# CarBot_Pedro.net
KiCad netlist of a schematic drawn in EAGLE
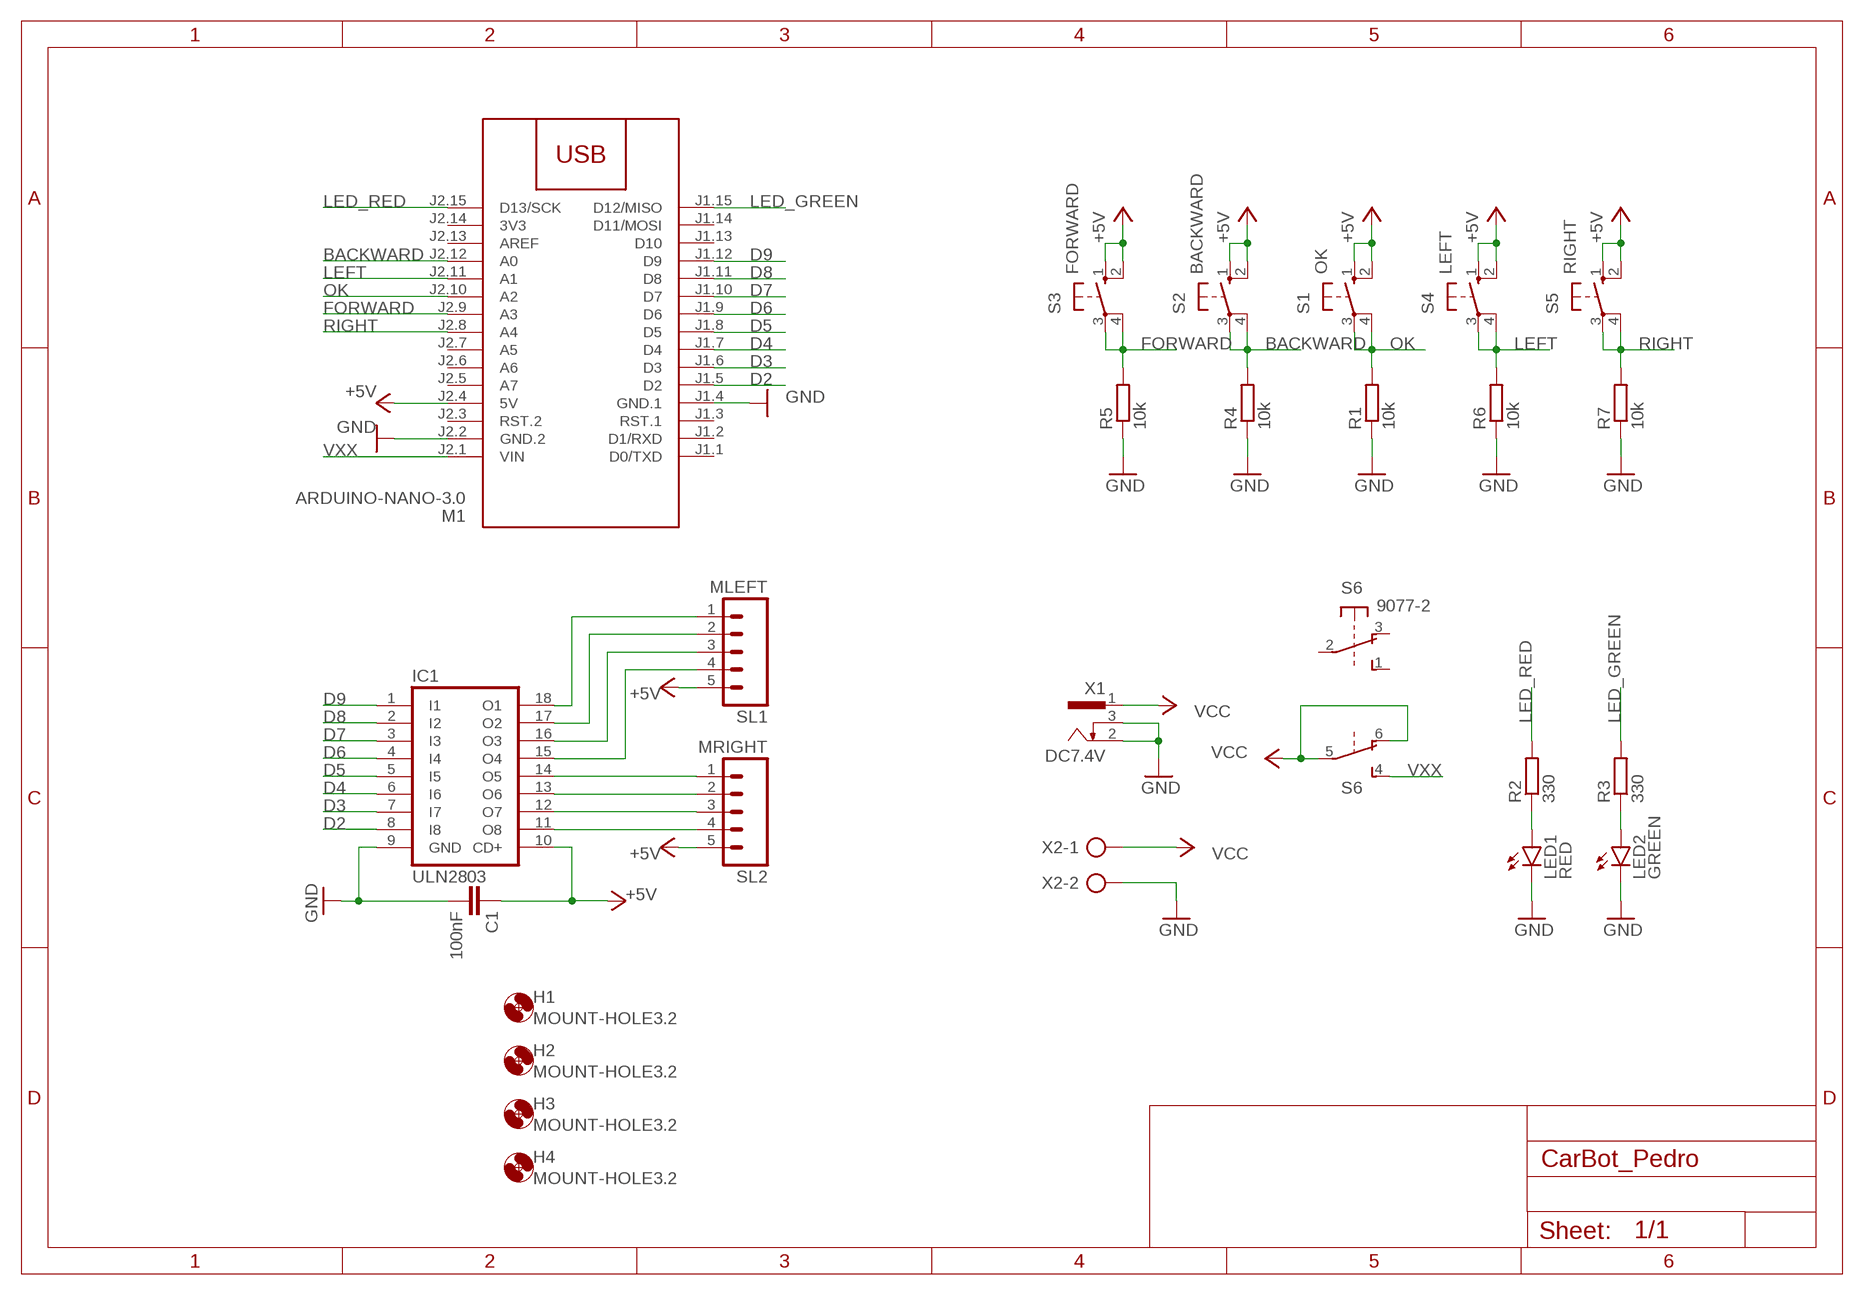
[diagram p0: schematic, sheet 1]

(export (version "E")
  (design (tool "Eeschema 10.0.6"))
  (components
    (comp (ref "C1")
      (value "100nF")
      (footprint "eagle-import:C025-030X050")
      (libsource (lib "eagle-import") (part "C-EU025-030X050"))
    )
    (comp (ref "H1")
      (value "MOUNT-HOLE3.2")
      (footprint "eagle-import:3,2")
      (libsource (lib "eagle-import") (part "MOUNT-HOLE3.2"))
    )
    (comp (ref "H2")
      (value "MOUNT-HOLE3.2")
      (footprint "eagle-import:3,2")
      (libsource (lib "eagle-import") (part "MOUNT-HOLE3.2"))
    )
    (comp (ref "H3")
      (value "MOUNT-HOLE3.2")
      (footprint "eagle-import:3,2")
      (libsource (lib "eagle-import") (part "MOUNT-HOLE3.2"))
    )
    (comp (ref "H4")
      (value "MOUNT-HOLE3.2")
      (footprint "eagle-import:3,2")
      (libsource (lib "eagle-import") (part "MOUNT-HOLE3.2"))
    )
    (comp (ref "IC1")
      (value "ULN2803")
      (footprint "eagle-import:DIL18")
      (libsource (lib "eagle-import") (part "ULN2803A"))
    )
    (comp (ref "LED1")
      (value "RED")
      (footprint "eagle-import:LED3MM")
      (libsource (lib "eagle-import") (part "LED3MM"))
    )
    (comp (ref "LED2")
      (value "GREEN")
      (footprint "eagle-import:LED3MM")
      (libsource (lib "eagle-import") (part "LED3MM"))
    )
    (comp (ref "M1")
      (value "ARDUINO-NANO-3.0")
      (footprint "eagle-import:ARDUINO-NANO-3.0")
      (libsource (lib "eagle-import") (part "ARDUINO-NANO-3.0"))
    )
    (comp (ref "R1")
      (value "10k")
      (footprint "eagle-import:0207_7")
      (libsource (lib "eagle-import") (part "R-EU_0207/7"))
    )
    (comp (ref "R2")
      (value "330")
      (footprint "eagle-import:0207_7")
      (libsource (lib "eagle-import") (part "R-EU_0207/7"))
    )
    (comp (ref "R3")
      (value "330")
      (footprint "eagle-import:0207_7")
      (libsource (lib "eagle-import") (part "R-EU_0207/7"))
    )
    (comp (ref "R4")
      (value "10k")
      (footprint "eagle-import:0207_7")
      (libsource (lib "eagle-import") (part "R-EU_0207/7"))
    )
    (comp (ref "R5")
      (value "10k")
      (footprint "eagle-import:0207_7")
      (libsource (lib "eagle-import") (part "R-EU_0207/7"))
    )
    (comp (ref "R6")
      (value "10k")
      (footprint "eagle-import:0207_7")
      (libsource (lib "eagle-import") (part "R-EU_0207/7"))
    )
    (comp (ref "R7")
      (value "10k")
      (footprint "eagle-import:0207_7")
      (libsource (lib "eagle-import") (part "R-EU_0207/7"))
    )
    (comp (ref "S1")
      (value "OK")
      (footprint "eagle-import:B3F-40XX")
      (fields (field (name "MF") "OMRON COMPONENTS USA") (field (name "MPN") "B3F-4000"))
      (libsource (lib "eagle-import") (part "40-XX"))
    )
    (comp (ref "S2")
      (value "BACKWARD")
      (footprint "eagle-import:B3F-40XX")
      (fields (field (name "MF") "OMRON COMPONENTS USA") (field (name "MPN") "B3F-4000"))
      (libsource (lib "eagle-import") (part "40-XX"))
    )
    (comp (ref "S3")
      (value "FORWARD")
      (footprint "eagle-import:B3F-40XX")
      (fields (field (name "MF") "OMRON COMPONENTS USA") (field (name "MPN") "B3F-4000"))
      (libsource (lib "eagle-import") (part "40-XX"))
    )
    (comp (ref "S4")
      (value "LEFT")
      (footprint "eagle-import:B3F-40XX")
      (fields (field (name "MF") "OMRON COMPONENTS USA") (field (name "MPN") "B3F-4000"))
      (libsource (lib "eagle-import") (part "40-XX"))
    )
    (comp (ref "S5")
      (value "RIGHT")
      (footprint "eagle-import:B3F-40XX")
      (fields (field (name "MF") "OMRON COMPONENTS USA") (field (name "MPN") "B3F-4000"))
      (libsource (lib "eagle-import") (part "40-XX"))
    )
    (comp (ref "S6")
      (value "9077-2")
      (footprint "eagle-import:9077-2")
      (libsource (lib "eagle-import") (part "9077-2"))
    )
    (comp (ref "SL1")
      (value "MLEFT")
      (footprint "eagle-import:05P")
      (libsource (lib "eagle-import") (part "M05"))
    )
    (comp (ref "SL2")
      (value "MRIGHT")
      (footprint "eagle-import:05P")
      (libsource (lib "eagle-import") (part "M05"))
    )
    (comp (ref "X1")
      (value "DC7.4V")
      (footprint "eagle-import:733980-62")
      (libsource (lib "eagle-import") (part "73398?0-62"))
    )
    (comp (ref "X2")
      (value "AK500/2-H")
      (footprint "eagle-import:AK500_2-H")
      (libsource (lib "eagle-import") (part "AK500/2-H"))
    )
  )
  (nets
    (net (code "1") (name "+5V") (class "Default")
      (node (ref "C1") (pin "1") (pinfunction "1_1") (pintype "passive"))
      (node (ref "IC1") (pin "10") (pinfunction "CD+_10") (pintype "passive"))
      (node (ref "M1") (pin "J2.4") (pinfunction "5V_J2.4") (pintype "power_in"))
      (node (ref "S1") (pin "1") (pinfunction "S_1") (pintype "passive"))
      (node (ref "S1") (pin "2") (pinfunction "S1_2") (pintype "passive"))
      (node (ref "S2") (pin "1") (pinfunction "S_1") (pintype "passive"))
      (node (ref "S2") (pin "2") (pinfunction "S1_2") (pintype "passive"))
      (node (ref "S3") (pin "1") (pinfunction "S_1") (pintype "passive"))
      (node (ref "S3") (pin "2") (pinfunction "S1_2") (pintype "passive"))
      (node (ref "S4") (pin "1") (pinfunction "S_1") (pintype "passive"))
      (node (ref "S4") (pin "2") (pinfunction "S1_2") (pintype "passive"))
      (node (ref "S5") (pin "1") (pinfunction "S_1") (pintype "passive"))
      (node (ref "S5") (pin "2") (pinfunction "S1_2") (pintype "passive"))
      (node (ref "SL1") (pin "5") (pinfunction "5_5") (pintype "passive"))
      (node (ref "SL2") (pin "5") (pinfunction "5_5") (pintype "passive"))
    )
    (net (code "2") (name "/3V3") (class "Default")
      (node (ref "M1") (pin "J2.14") (pinfunction "3V3_J2.14") (pintype "power_in"))
    )
    (net (code "3") (name "/BACKWARD") (class "Default")
      (node (ref "M1") (pin "J2.12") (pinfunction "A0_J2.12") (pintype "bidirectional"))
      (node (ref "R4") (pin "2") (pinfunction "2_2") (pintype "passive"))
      (node (ref "S2") (pin "3") (pinfunction "P_3") (pintype "passive"))
      (node (ref "S2") (pin "4") (pinfunction "P1_4") (pintype "passive"))
    )
    (net (code "4") (name "/D2") (class "Default")
      (node (ref "IC1") (pin "8") (pinfunction "I8_8") (pintype "input"))
      (node (ref "M1") (pin "J1.5") (pinfunction "D2_J1.5") (pintype "bidirectional"))
    )
    (net (code "5") (name "/D3") (class "Default")
      (node (ref "IC1") (pin "7") (pinfunction "I7_7") (pintype "input"))
      (node (ref "M1") (pin "J1.6") (pinfunction "D3_J1.6") (pintype "bidirectional"))
    )
    (net (code "6") (name "/D4") (class "Default")
      (node (ref "IC1") (pin "6") (pinfunction "I6_6") (pintype "input"))
      (node (ref "M1") (pin "J1.7") (pinfunction "D4_J1.7") (pintype "bidirectional"))
    )
    (net (code "7") (name "/D5") (class "Default")
      (node (ref "IC1") (pin "5") (pinfunction "I5_5") (pintype "input"))
      (node (ref "M1") (pin "J1.8") (pinfunction "D5_J1.8") (pintype "bidirectional"))
    )
    (net (code "8") (name "/D6") (class "Default")
      (node (ref "IC1") (pin "4") (pinfunction "I4_4") (pintype "input"))
      (node (ref "M1") (pin "J1.9") (pinfunction "D6_J1.9") (pintype "bidirectional"))
    )
    (net (code "9") (name "/D7") (class "Default")
      (node (ref "IC1") (pin "3") (pinfunction "I3_3") (pintype "input"))
      (node (ref "M1") (pin "J1.10") (pinfunction "D7_J1.10") (pintype "bidirectional"))
    )
    (net (code "10") (name "/D8") (class "Default")
      (node (ref "IC1") (pin "2") (pinfunction "I2_2") (pintype "input"))
      (node (ref "M1") (pin "J1.11") (pinfunction "D8_J1.11") (pintype "bidirectional"))
    )
    (net (code "11") (name "/D9") (class "Default")
      (node (ref "IC1") (pin "1") (pinfunction "I1_1") (pintype "input"))
      (node (ref "M1") (pin "J1.12") (pinfunction "D9_J1.12") (pintype "bidirectional"))
    )
    (net (code "12") (name "/FORWARD") (class "Default")
      (node (ref "M1") (pin "J2.9") (pinfunction "A3_J2.9") (pintype "bidirectional"))
      (node (ref "R5") (pin "2") (pinfunction "2_2") (pintype "passive"))
      (node (ref "S3") (pin "3") (pinfunction "P_3") (pintype "passive"))
      (node (ref "S3") (pin "4") (pinfunction "P1_4") (pintype "passive"))
    )
    (net (code "13") (name "/LED_GREEN") (class "Default")
      (node (ref "M1") (pin "J1.15") (pinfunction "D12/MISO_J1.15") (pintype "bidirectional"))
      (node (ref "R3") (pin "2") (pinfunction "2_2") (pintype "passive"))
    )
    (net (code "14") (name "/LED_RED") (class "Default")
      (node (ref "M1") (pin "J2.15") (pinfunction "D13/SCK_J2.15") (pintype "bidirectional"))
      (node (ref "R2") (pin "2") (pinfunction "2_2") (pintype "passive"))
    )
    (net (code "15") (name "/LEFT") (class "Default")
      (node (ref "M1") (pin "J2.11") (pinfunction "A1_J2.11") (pintype "bidirectional"))
      (node (ref "R6") (pin "2") (pinfunction "2_2") (pintype "passive"))
      (node (ref "S4") (pin "3") (pinfunction "P_3") (pintype "passive"))
      (node (ref "S4") (pin "4") (pinfunction "P1_4") (pintype "passive"))
    )
    (net (code "16") (name "/OK") (class "Default")
      (node (ref "M1") (pin "J2.10") (pinfunction "A2_J2.10") (pintype "bidirectional"))
      (node (ref "R1") (pin "2") (pinfunction "2_2") (pintype "passive"))
      (node (ref "S1") (pin "3") (pinfunction "P_3") (pintype "passive"))
      (node (ref "S1") (pin "4") (pinfunction "P1_4") (pintype "passive"))
    )
    (net (code "17") (name "/RIGHT") (class "Default")
      (node (ref "M1") (pin "J2.8") (pinfunction "A4_J2.8") (pintype "bidirectional"))
      (node (ref "R7") (pin "2") (pinfunction "2_2") (pintype "passive"))
      (node (ref "S5") (pin "3") (pinfunction "P_3") (pintype "passive"))
      (node (ref "S5") (pin "4") (pinfunction "P1_4") (pintype "passive"))
    )
    (net (code "18") (name "/VXX") (class "Default")
      (node (ref "M1") (pin "J2.1") (pinfunction "VIN_J2.1") (pintype "power_in"))
      (node (ref "S6") (pin "4") (pinfunction "S_4") (pintype "passive"))
    )
    (net (code "19") (name "GND") (class "Default")
      (node (ref "C1") (pin "2") (pinfunction "2_2") (pintype "passive"))
      (node (ref "IC1") (pin "9") (pinfunction "GND_9") (pintype "power_in"))
      (node (ref "LED1") (pin "K") (pinfunction "C_K") (pintype "passive"))
      (node (ref "LED2") (pin "K") (pinfunction "C_K") (pintype "passive"))
      (node (ref "M1") (pin "J1.4") (pinfunction "GND.1_J1.4") (pintype "power_in"))
      (node (ref "M1") (pin "J2.2") (pinfunction "GND.2_J2.2") (pintype "power_in"))
      (node (ref "R1") (pin "1") (pinfunction "1_1") (pintype "passive"))
      (node (ref "R4") (pin "1") (pinfunction "1_1") (pintype "passive"))
      (node (ref "R5") (pin "1") (pinfunction "1_1") (pintype "passive"))
      (node (ref "R6") (pin "1") (pinfunction "1_1") (pintype "passive"))
      (node (ref "R7") (pin "1") (pinfunction "1_1") (pintype "passive"))
      (node (ref "X1") (pin "2") (pinfunction "2_2") (pintype "passive"))
      (node (ref "X1") (pin "3") (pinfunction "3_3") (pintype "passive"))
      (node (ref "X2") (pin "2") (pinfunction "KL_2") (pintype "passive"))
    )
    (net (code "20") (name "Net-(IC1-O1)") (class "Default")
      (node (ref "IC1") (pin "18") (pinfunction "O1_18") (pintype "open_collector"))
      (node (ref "SL1") (pin "1") (pinfunction "1_1") (pintype "passive"))
    )
    (net (code "21") (name "Net-(IC1-O2)") (class "Default")
      (node (ref "IC1") (pin "17") (pinfunction "O2_17") (pintype "open_collector"))
      (node (ref "SL1") (pin "2") (pinfunction "2_2") (pintype "passive"))
    )
    (net (code "22") (name "Net-(IC1-O3)") (class "Default")
      (node (ref "IC1") (pin "16") (pinfunction "O3_16") (pintype "open_collector"))
      (node (ref "SL1") (pin "3") (pinfunction "3_3") (pintype "passive"))
    )
    (net (code "23") (name "Net-(IC1-O4)") (class "Default")
      (node (ref "IC1") (pin "15") (pinfunction "O4_15") (pintype "open_collector"))
      (node (ref "SL1") (pin "4") (pinfunction "4_4") (pintype "passive"))
    )
    (net (code "24") (name "Net-(IC1-O5)") (class "Default")
      (node (ref "IC1") (pin "14") (pinfunction "O5_14") (pintype "open_collector"))
      (node (ref "SL2") (pin "1") (pinfunction "1_1") (pintype "passive"))
    )
    (net (code "25") (name "Net-(IC1-O6)") (class "Default")
      (node (ref "IC1") (pin "13") (pinfunction "O6_13") (pintype "open_collector"))
      (node (ref "SL2") (pin "2") (pinfunction "2_2") (pintype "passive"))
    )
    (net (code "26") (name "Net-(IC1-O7)") (class "Default")
      (node (ref "IC1") (pin "12") (pinfunction "O7_12") (pintype "open_collector"))
      (node (ref "SL2") (pin "3") (pinfunction "3_3") (pintype "passive"))
    )
    (net (code "27") (name "Net-(IC1-O8)") (class "Default")
      (node (ref "IC1") (pin "11") (pinfunction "O8_11") (pintype "open_collector"))
      (node (ref "SL2") (pin "4") (pinfunction "4_4") (pintype "passive"))
    )
    (net (code "28") (name "Net-(LED1-PadA)") (class "Default")
      (node (ref "LED1") (pin "A") (pinfunction "A_A") (pintype "passive"))
      (node (ref "R2") (pin "1") (pinfunction "1_1") (pintype "passive"))
    )
    (net (code "29") (name "Net-(LED2-PadA)") (class "Default")
      (node (ref "LED2") (pin "A") (pinfunction "A_A") (pintype "passive"))
      (node (ref "R3") (pin "1") (pinfunction "1_1") (pintype "passive"))
    )
    (net (code "30") (name "VCC") (class "Default")
      (node (ref "S6") (pin "5") (pinfunction "P_5") (pintype "passive"))
      (node (ref "S6") (pin "6") (pinfunction "O_6") (pintype "passive"))
      (node (ref "X1") (pin "1") (pinfunction "1_1") (pintype "passive"))
      (node (ref "X2") (pin "1") (pinfunction "KL_1") (pintype "passive"))
    )
    (net (code "31") (name "unconnected-(M1-A5-PadJ2.7)") (class "Default")
      (node (ref "M1") (pin "J2.7") (pinfunction "A5_J2.7") (pintype "bidirectional"))
    )
    (net (code "32") (name "unconnected-(M1-A6-PadJ2.6)") (class "Default")
      (node (ref "M1") (pin "J2.6") (pinfunction "A6_J2.6") (pintype "bidirectional"))
    )
    (net (code "33") (name "unconnected-(M1-A7-PadJ2.5)") (class "Default")
      (node (ref "M1") (pin "J2.5") (pinfunction "A7_J2.5") (pintype "bidirectional"))
    )
    (net (code "34") (name "unconnected-(M1-AREF-PadJ2.13)") (class "Default")
      (node (ref "M1") (pin "J2.13") (pinfunction "AREF_J2.13") (pintype "bidirectional"))
    )
    (net (code "35") (name "unconnected-(M1-D0{slash}TXD-PadJ1.1)") (class "Default")
      (node (ref "M1") (pin "J1.1") (pinfunction "D0/TXD_J1.1") (pintype "bidirectional"))
    )
    (net (code "36") (name "unconnected-(M1-D1{slash}RXD-PadJ1.2)") (class "Default")
      (node (ref "M1") (pin "J1.2") (pinfunction "D1/RXD_J1.2") (pintype "bidirectional"))
    )
    (net (code "37") (name "unconnected-(M1-D10-PadJ1.13)") (class "Default")
      (node (ref "M1") (pin "J1.13") (pinfunction "D10_J1.13") (pintype "bidirectional"))
    )
    (net (code "38") (name "unconnected-(M1-D11{slash}MOSI-PadJ1.14)") (class "Default")
      (node (ref "M1") (pin "J1.14") (pinfunction "D11/MOSI_J1.14") (pintype "bidirectional"))
    )
    (net (code "39") (name "unconnected-(M1-RST.1-PadJ1.3)") (class "Default")
      (node (ref "M1") (pin "J1.3") (pinfunction "RST.1_J1.3") (pintype "bidirectional"))
    )
    (net (code "40") (name "unconnected-(M1-RST.2-PadJ2.3)") (class "Default")
      (node (ref "M1") (pin "J2.3") (pinfunction "RST.2_J2.3") (pintype "bidirectional"))
    )
    (net (code "41") (name "unconnected-(S6A-O-Pad3)") (class "Default")
      (node (ref "S6") (pin "3") (pinfunction "O_3") (pintype "passive"))
    )
    (net (code "42") (name "unconnected-(S6A-P-Pad2)") (class "Default")
      (node (ref "S6") (pin "2") (pinfunction "P_2") (pintype "passive"))
    )
    (net (code "43") (name "unconnected-(S6A-S-Pad1)") (class "Default")
      (node (ref "S6") (pin "1") (pinfunction "S_1") (pintype "passive"))
    )
  )
)
